# DD2090_4CAM_FFC_IR_Dot_Projector_IR_LED.net
KiCad netlist of a schematic drawn in Altium Designer
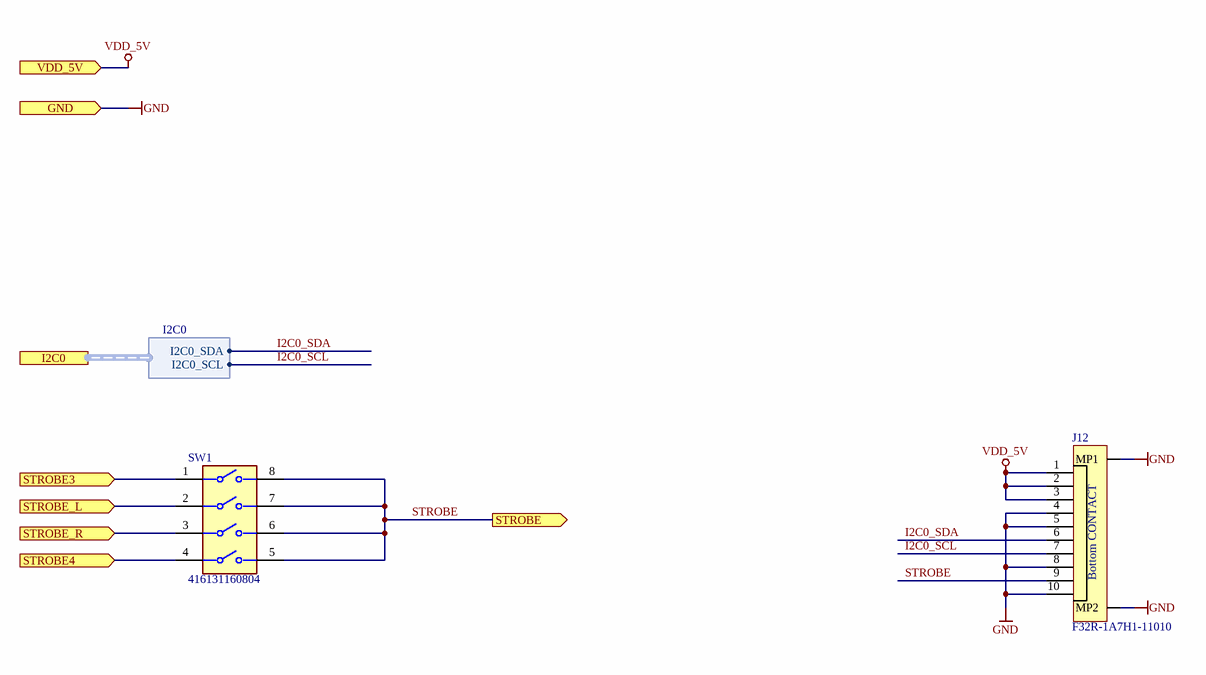
[diagram p0: DD2090_4CAM_FFC_IR_Dot_Projector_IR_LED.SchDoc]

(export (version "E")
  (design (tool "Eeschema 10.0.6"))
  (components
    (comp (ref "J12")
      (value "F32R-1A7H1-11010")
      (footprint "F32R-1A7H1-11010")
      (description "FPC/FFC Connector Socket 10 Position 0.5mm Bottom Contact Solder Right Angle Surface Mount T/R")
      (libsource (lib "Luxonis LLC") (part "F32R-1A7H1-11010"))
    )
    (comp (ref "SW1")
      (value "416131160804")
      (footprint "FP-416131160804-MFG")
      (libsource (lib "Luxonis LLC") (part "c3c4c2ac9515373cfee496e575704c1"))
    )
  )
  (nets
    (net (code "2") (name "/I2C0_SCL") (class "Default")
      (node (ref "J12") (pin "7") (pinfunction "7_7") (pintype "passive"))
    )
    (net (code "3") (name "/I2C0_SDA") (class "Default")
      (node (ref "J12") (pin "6") (pinfunction "6_6") (pintype "passive"))
    )
    (net (code "4") (name "/STROBE") (class "Default")
      (node (ref "J12") (pin "9") (pinfunction "9_9") (pintype "passive"))
      (node (ref "SW1") (pin "5") (pinfunction "5_5") (pintype "passive"))
      (node (ref "SW1") (pin "6") (pinfunction "6_6") (pintype "passive"))
      (node (ref "SW1") (pin "7") (pinfunction "7_7") (pintype "passive"))
      (node (ref "SW1") (pin "8") (pinfunction "8_8") (pintype "passive"))
    )
    (net (code "5") (name "/STROBE3") (class "Default")
      (node (ref "SW1") (pin "1") (pinfunction "1_1") (pintype "passive"))
    )
    (net (code "6") (name "/STROBE4") (class "Default")
      (node (ref "SW1") (pin "4") (pinfunction "4_4") (pintype "passive"))
    )
    (net (code "7") (name "/STROBE_L") (class "Default")
      (node (ref "SW1") (pin "2") (pinfunction "2_2") (pintype "passive"))
    )
    (net (code "8") (name "/STROBE_R") (class "Default")
      (node (ref "SW1") (pin "3") (pinfunction "3_3") (pintype "passive"))
    )
    (net (code "10") (name "GND") (class "Default")
      (node (ref "J12") (pin "10") (pinfunction "10_10") (pintype "passive"))
      (node (ref "J12") (pin "4") (pinfunction "4_4") (pintype "passive"))
      (node (ref "J12") (pin "5") (pinfunction "5_5") (pintype "passive"))
      (node (ref "J12") (pin "8") (pinfunction "8_8") (pintype "passive"))
      (node (ref "J12") (pin "MP1") (pinfunction "MP1_MP1") (pintype "passive"))
      (node (ref "J12") (pin "MP2") (pinfunction "MP2_MP2") (pintype "passive"))
    )
    (net (code "11") (name "VDD_5V") (class "Default")
      (node (ref "J12") (pin "1") (pinfunction "1_1") (pintype "passive"))
      (node (ref "J12") (pin "2") (pinfunction "2_2") (pintype "passive"))
      (node (ref "J12") (pin "3") (pinfunction "3_3") (pintype "passive"))
    )
  )
)
